# rc2014_6502.net
KiCad netlist of a schematic drawn in EAGLE
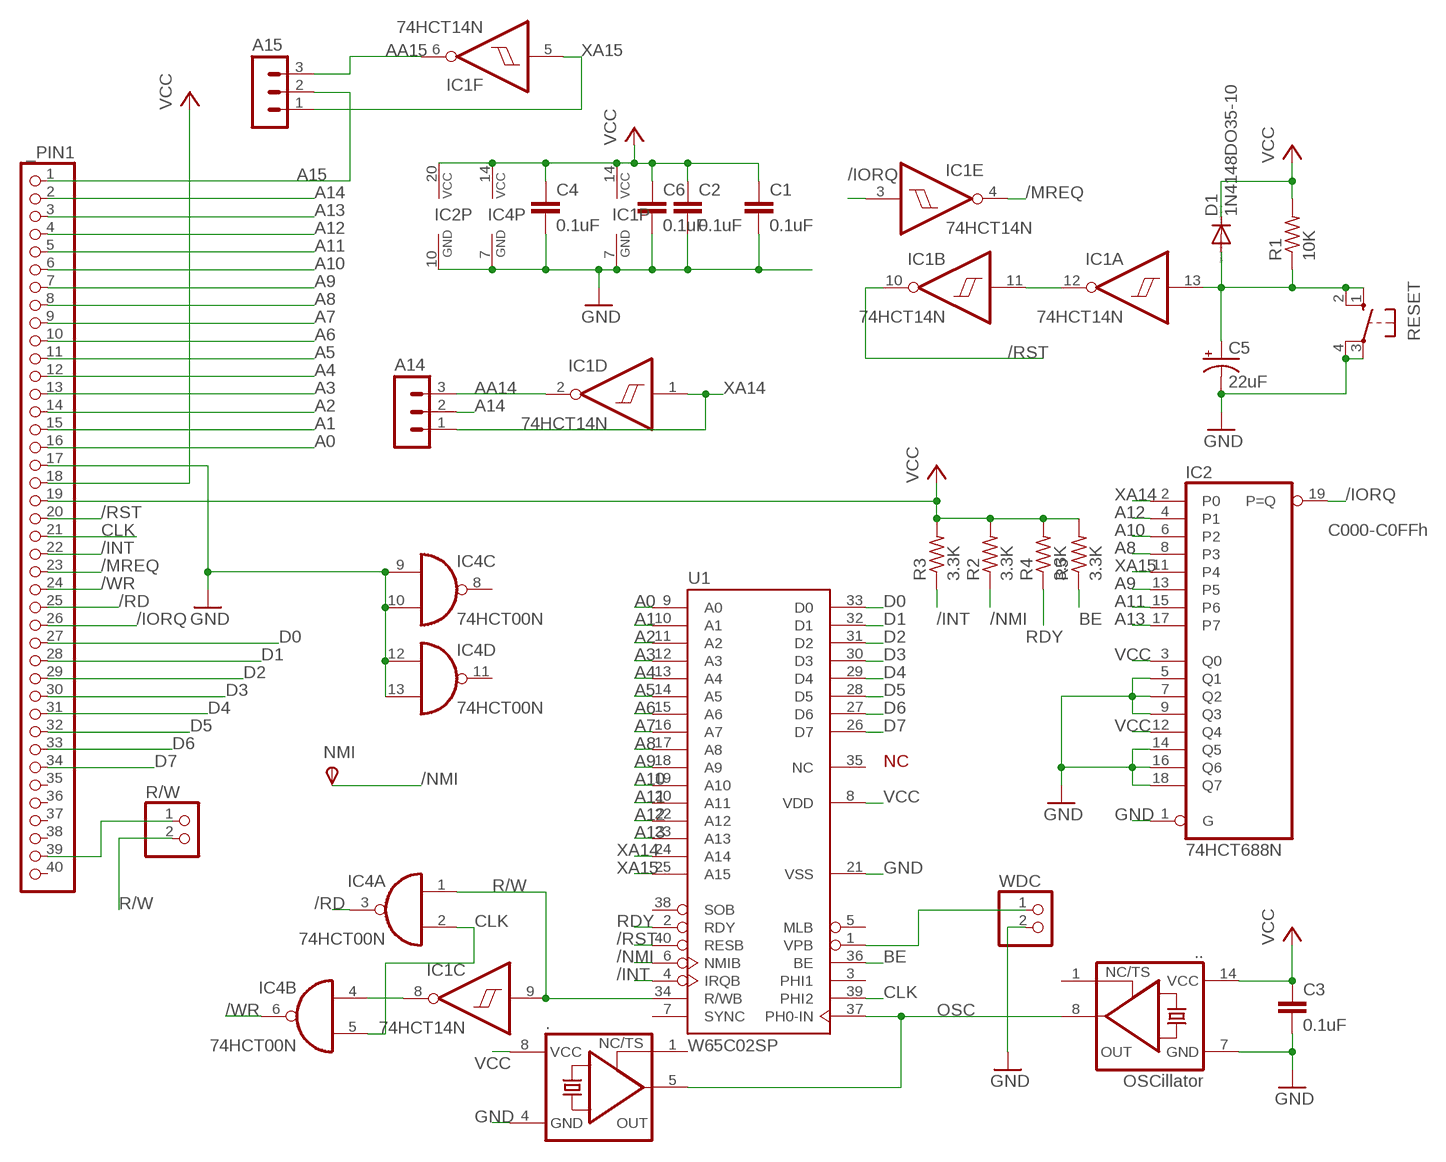
[diagram p0: schematic, sheet 1]

(export (version "E")
  (design (tool "Eeschema 10.0.6"))
  (components
    (comp (ref ".")
      (value "XO-8")
      (footprint "eagle-import:DIL08S")
      (libsource (lib "eagle-import") (part "XO-8"))
    )
    (comp (ref "..")
      (value "OSCillator")
      (footprint "eagle-import:DIL14S")
      (libsource (lib "eagle-import") (part "XO-14"))
    )
    (comp (ref "A14")
      (value "MA03-1")
      (footprint "eagle-import:MA03-1")
      (libsource (lib "eagle-import") (part "MA03-1"))
    )
    (comp (ref "A15")
      (value "MA03-1")
      (footprint "eagle-import:MA03-1")
      (libsource (lib "eagle-import") (part "MA03-1"))
    )
    (comp (ref "C1")
      (value "0.1uF")
      (footprint "eagle-import:C050-024X044")
      (libsource (lib "eagle-import") (part "C-EU050-024X044"))
    )
    (comp (ref "C2")
      (value "0.1uF")
      (footprint "eagle-import:C050-024X044")
      (libsource (lib "eagle-import") (part "C-EU050-024X044"))
    )
    (comp (ref "C3")
      (value "0.1uF")
      (footprint "eagle-import:C050-024X044")
      (libsource (lib "eagle-import") (part "C-EU050-024X044"))
    )
    (comp (ref "C4")
      (value "0.1uF")
      (footprint "eagle-import:C050-024X044")
      (libsource (lib "eagle-import") (part "C-EU050-024X044"))
    )
    (comp (ref "C5")
      (value "22uF")
      (footprint "eagle-import:TAP5-80")
      (libsource (lib "eagle-import") (part "CPOL-USTAP5-80"))
    )
    (comp (ref "C6")
      (value "0.1uF")
      (footprint "eagle-import:C050-024X044")
      (libsource (lib "eagle-import") (part "C-EU050-024X044"))
    )
    (comp (ref "D1")
      (value "1N4148DO35-10")
      (footprint "eagle-import:DO35-10")
      (libsource (lib "eagle-import") (part "1N4148DO35-10"))
    )
    (comp (ref "IC1")
      (value "74HCT14N")
      (footprint "eagle-import:DIL14")
      (libsource (lib "eagle-import") (part "7414NHCT"))
    )
    (comp (ref "IC2")
      (value "74HCT688N")
      (footprint "eagle-import:DIL20")
      (libsource (lib "eagle-import") (part "74688NHCT"))
    )
    (comp (ref "IC4")
      (value "74HCT00N")
      (footprint "eagle-import:DIL14")
      (libsource (lib "eagle-import") (part "7400NHCT"))
    )
    (comp (ref "NMI")
      (value "TPSPAD1-13")
      (footprint "eagle-import:P1-13")
      (libsource (lib "eagle-import") (part "TPSPAD1-13"))
    )
    (comp (ref "R/W")
      (value "PINHD-1X2")
      (footprint "eagle-import:1X02")
      (libsource (lib "eagle-import") (part "PINHD-1X2"))
    )
    (comp (ref "R1")
      (value "10K")
      (footprint "eagle-import:0207_10")
      (libsource (lib "eagle-import") (part "R-US_0207/10"))
    )
    (comp (ref "R2")
      (value "3.3K")
      (footprint "eagle-import:0207_10")
      (libsource (lib "eagle-import") (part "R-US_0207/10"))
    )
    (comp (ref "R3")
      (value "3.3K")
      (footprint "eagle-import:0207_10")
      (libsource (lib "eagle-import") (part "R-US_0207/10"))
    )
    (comp (ref "R4")
      (value "3.3K")
      (footprint "eagle-import:0207_10")
      (libsource (lib "eagle-import") (part "R-US_0207/10"))
    )
    (comp (ref "R5")
      (value "3.3K")
      (footprint "eagle-import:0207_10")
      (libsource (lib "eagle-import") (part "R-US_0207/10"))
    )
    (comp (ref "RESET")
      (value "10-XX")
      (footprint "eagle-import:B3F-10XX")
      (fields (field (name "MPN") "B3F-1000"))
      (libsource (lib "eagle-import") (part "10-XX"))
    )
    (comp (ref "U1")
      (value "W65C02SP")
      (footprint "eagle-import:DIP-40")
      (libsource (lib "eagle-import") (part "W65C02SP"))
    )
    (comp (ref "WDC")
      (value "PINHD-1X2")
      (footprint "eagle-import:1X02")
      (libsource (lib "eagle-import") (part "PINHD-1X2"))
    )
    (comp (ref "_PIN1")
      (value "PINHD-1X40")
      (footprint "eagle-import:1X40")
      (libsource (lib "eagle-import") (part "PINHD-1X40"))
    )
  )
  (nets
    (net (code "1") (name "/A0") (class "Default")
      (node (ref "U1") (pin "9") (pinfunction "A0_9") (pintype "bidirectional"))
      (node (ref "_PIN1") (pin "16") (pinfunction "16_16") (pintype "passive"))
    )
    (net (code "2") (name "/A1") (class "Default")
      (node (ref "U1") (pin "10") (pinfunction "A1_10") (pintype "bidirectional"))
      (node (ref "_PIN1") (pin "15") (pinfunction "15_15") (pintype "passive"))
    )
    (net (code "3") (name "/A2") (class "Default")
      (node (ref "U1") (pin "11") (pinfunction "A2_11") (pintype "bidirectional"))
      (node (ref "_PIN1") (pin "14") (pinfunction "14_14") (pintype "passive"))
    )
    (net (code "4") (name "/A3") (class "Default")
      (node (ref "U1") (pin "12") (pinfunction "A3_12") (pintype "bidirectional"))
      (node (ref "_PIN1") (pin "13") (pinfunction "13_13") (pintype "passive"))
    )
    (net (code "5") (name "/A4") (class "Default")
      (node (ref "U1") (pin "13") (pinfunction "A4_13") (pintype "bidirectional"))
      (node (ref "_PIN1") (pin "12") (pinfunction "12_12") (pintype "passive"))
    )
    (net (code "6") (name "/A5") (class "Default")
      (node (ref "U1") (pin "14") (pinfunction "A5_14") (pintype "bidirectional"))
      (node (ref "_PIN1") (pin "11") (pinfunction "11_11") (pintype "passive"))
    )
    (net (code "7") (name "/A6") (class "Default")
      (node (ref "U1") (pin "15") (pinfunction "A6_15") (pintype "bidirectional"))
      (node (ref "_PIN1") (pin "10") (pinfunction "10_10") (pintype "passive"))
    )
    (net (code "8") (name "/A7") (class "Default")
      (node (ref "U1") (pin "16") (pinfunction "A7_16") (pintype "bidirectional"))
      (node (ref "_PIN1") (pin "9") (pinfunction "9_9") (pintype "passive"))
    )
    (net (code "9") (name "/A8") (class "Default")
      (node (ref "IC2") (pin "8") (pinfunction "P3_8") (pintype "input"))
      (node (ref "U1") (pin "17") (pinfunction "A8_17") (pintype "bidirectional"))
      (node (ref "_PIN1") (pin "8") (pinfunction "8_8") (pintype "passive"))
    )
    (net (code "10") (name "/A9") (class "Default")
      (node (ref "IC2") (pin "13") (pinfunction "P5_13") (pintype "input"))
      (node (ref "U1") (pin "18") (pinfunction "A9_18") (pintype "bidirectional"))
      (node (ref "_PIN1") (pin "7") (pinfunction "7_7") (pintype "passive"))
    )
    (net (code "11") (name "/A10") (class "Default")
      (node (ref "IC2") (pin "6") (pinfunction "P2_6") (pintype "input"))
      (node (ref "U1") (pin "19") (pinfunction "A10_19") (pintype "bidirectional"))
      (node (ref "_PIN1") (pin "6") (pinfunction "6_6") (pintype "passive"))
    )
    (net (code "12") (name "/A11") (class "Default")
      (node (ref "IC2") (pin "15") (pinfunction "P6_15") (pintype "input"))
      (node (ref "U1") (pin "20") (pinfunction "A11_20") (pintype "bidirectional"))
      (node (ref "_PIN1") (pin "5") (pinfunction "5_5") (pintype "passive"))
    )
    (net (code "13") (name "/A12") (class "Default")
      (node (ref "IC2") (pin "4") (pinfunction "P1_4") (pintype "input"))
      (node (ref "U1") (pin "22") (pinfunction "A12_22") (pintype "bidirectional"))
      (node (ref "_PIN1") (pin "4") (pinfunction "4_4") (pintype "passive"))
    )
    (net (code "14") (name "/A13") (class "Default")
      (node (ref "IC2") (pin "17") (pinfunction "P7_17") (pintype "input"))
      (node (ref "U1") (pin "23") (pinfunction "A13_23") (pintype "bidirectional"))
      (node (ref "_PIN1") (pin "3") (pinfunction "3_3") (pintype "passive"))
    )
    (net (code "15") (name "/A14") (class "Default")
      (node (ref "A14") (pin "2") (pinfunction "2_2") (pintype "passive"))
      (node (ref "_PIN1") (pin "2") (pinfunction "2_2") (pintype "passive"))
    )
    (net (code "16") (name "/A15") (class "Default")
      (node (ref "A15") (pin "2") (pinfunction "2_2") (pintype "passive"))
      (node (ref "_PIN1") (pin "1") (pinfunction "1_1") (pintype "passive"))
    )
    (net (code "17") (name "/AA14") (class "Default")
      (node (ref "A14") (pin "3") (pinfunction "3_3") (pintype "passive"))
      (node (ref "IC1") (pin "2") (pinfunction "O_2") (pintype "output"))
    )
    (net (code "18") (name "/AA15") (class "Default")
      (node (ref "A15") (pin "3") (pinfunction "3_3") (pintype "passive"))
      (node (ref "IC1") (pin "6") (pinfunction "O_6") (pintype "output"))
    )
    (net (code "19") (name "/BE") (class "Default")
      (node (ref "R5") (pin "1") (pinfunction "1_1") (pintype "passive"))
      (node (ref "U1") (pin "36") (pinfunction "BE_36") (pintype "input"))
    )
    (net (code "20") (name "/CLK") (class "Default")
      (node (ref "IC4") (pin "2") (pinfunction "I1_2") (pintype "input"))
      (node (ref "IC4") (pin "5") (pinfunction "I1_5") (pintype "input"))
      (node (ref "U1") (pin "39") (pinfunction "PHI2_39") (pintype "output"))
      (node (ref "_PIN1") (pin "21") (pinfunction "21_21") (pintype "passive"))
    )
    (net (code "21") (name "/D0") (class "Default")
      (node (ref "U1") (pin "33") (pinfunction "D0_33") (pintype "bidirectional"))
      (node (ref "_PIN1") (pin "27") (pinfunction "27_27") (pintype "passive"))
    )
    (net (code "22") (name "/D1") (class "Default")
      (node (ref "U1") (pin "32") (pinfunction "D1_32") (pintype "bidirectional"))
      (node (ref "_PIN1") (pin "28") (pinfunction "28_28") (pintype "passive"))
    )
    (net (code "23") (name "/D2") (class "Default")
      (node (ref "U1") (pin "31") (pinfunction "D2_31") (pintype "bidirectional"))
      (node (ref "_PIN1") (pin "29") (pinfunction "29_29") (pintype "passive"))
    )
    (net (code "24") (name "/D3") (class "Default")
      (node (ref "U1") (pin "30") (pinfunction "D3_30") (pintype "bidirectional"))
      (node (ref "_PIN1") (pin "30") (pinfunction "30_30") (pintype "passive"))
    )
    (net (code "25") (name "/D4") (class "Default")
      (node (ref "U1") (pin "29") (pinfunction "D4_29") (pintype "bidirectional"))
      (node (ref "_PIN1") (pin "31") (pinfunction "31_31") (pintype "passive"))
    )
    (net (code "26") (name "/D5") (class "Default")
      (node (ref "U1") (pin "28") (pinfunction "D5_28") (pintype "bidirectional"))
      (node (ref "_PIN1") (pin "32") (pinfunction "32_32") (pintype "passive"))
    )
    (net (code "27") (name "/D6") (class "Default")
      (node (ref "U1") (pin "27") (pinfunction "D6_27") (pintype "bidirectional"))
      (node (ref "_PIN1") (pin "33") (pinfunction "33_33") (pintype "passive"))
    )
    (net (code "28") (name "/D7") (class "Default")
      (node (ref "U1") (pin "26") (pinfunction "D7_26") (pintype "bidirectional"))
      (node (ref "_PIN1") (pin "34") (pinfunction "34_34") (pintype "passive"))
    )
    (net (code "29") (name "/OSC") (class "Default")
      (node (ref ".") (pin "5") (pinfunction "OUT_5") (pintype "output"))
      (node (ref "..") (pin "8") (pinfunction "OUT_8") (pintype "output"))
      (node (ref "U1") (pin "37") (pinfunction "PH0-IN_37") (pintype "input"))
    )
    (net (code "30") (name "/RDY") (class "Default")
      (node (ref "R4") (pin "1") (pinfunction "1_1") (pintype "passive"))
      (node (ref "U1") (pin "2") (pinfunction "RDY_2") (pintype "bidirectional"))
    )
    (net (code "31") (name "/R{slash}W") (class "Default")
      (node (ref "IC1") (pin "9") (pinfunction "I_9") (pintype "input"))
      (node (ref "IC4") (pin "1") (pinfunction "I0_1") (pintype "input"))
      (node (ref "R/W") (pin "2") (pinfunction "2_2") (pintype "passive"))
      (node (ref "U1") (pin "34") (pinfunction "R/WB_34") (pintype "output"))
    )
    (net (code "32") (name "/XA14") (class "Default")
      (node (ref "A14") (pin "1") (pinfunction "1_1") (pintype "passive"))
      (node (ref "IC1") (pin "1") (pinfunction "I_1") (pintype "input"))
      (node (ref "IC2") (pin "2") (pinfunction "P0_2") (pintype "input"))
      (node (ref "U1") (pin "24") (pinfunction "A14_24") (pintype "bidirectional"))
    )
    (net (code "33") (name "/XA15") (class "Default")
      (node (ref "A15") (pin "1") (pinfunction "1_1") (pintype "passive"))
      (node (ref "IC1") (pin "5") (pinfunction "I_5") (pintype "input"))
      (node (ref "IC2") (pin "11") (pinfunction "P4_11") (pintype "input"))
      (node (ref "U1") (pin "25") (pinfunction "A15_25") (pintype "bidirectional"))
    )
    (net (code "34") (name "/{slash}INT") (class "Default")
      (node (ref "R3") (pin "1") (pinfunction "1_1") (pintype "passive"))
      (node (ref "U1") (pin "4") (pinfunction "IRQB_4") (pintype "input"))
      (node (ref "_PIN1") (pin "22") (pinfunction "22_22") (pintype "passive"))
    )
    (net (code "35") (name "/{slash}IORQ") (class "Default")
      (node (ref "IC1") (pin "3") (pinfunction "I_3") (pintype "input"))
      (node (ref "IC2") (pin "19") (pinfunction "P=Q_19") (pintype "output"))
      (node (ref "_PIN1") (pin "26") (pinfunction "26_26") (pintype "passive"))
    )
    (net (code "36") (name "/{slash}MREQ") (class "Default")
      (node (ref "IC1") (pin "4") (pinfunction "O_4") (pintype "output"))
      (node (ref "_PIN1") (pin "23") (pinfunction "23_23") (pintype "passive"))
    )
    (net (code "37") (name "/{slash}NMI") (class "Default")
      (node (ref "NMI") (pin "TP") (pinfunction "PP_TP") (pintype "input"))
      (node (ref "R2") (pin "1") (pinfunction "1_1") (pintype "passive"))
      (node (ref "U1") (pin "6") (pinfunction "NMIB_6") (pintype "input"))
    )
    (net (code "38") (name "/{slash}RD") (class "Default")
      (node (ref "IC4") (pin "3") (pinfunction "O_3") (pintype "output"))
      (node (ref "_PIN1") (pin "25") (pinfunction "25_25") (pintype "passive"))
    )
    (net (code "39") (name "/{slash}RST") (class "Default")
      (node (ref "IC1") (pin "10") (pinfunction "O_10") (pintype "output"))
      (node (ref "U1") (pin "40") (pinfunction "RESB_40") (pintype "input"))
      (node (ref "_PIN1") (pin "20") (pinfunction "20_20") (pintype "passive"))
    )
    (net (code "40") (name "/{slash}WR") (class "Default")
      (node (ref "IC4") (pin "6") (pinfunction "O_6") (pintype "output"))
      (node (ref "_PIN1") (pin "24") (pinfunction "24_24") (pintype "passive"))
    )
    (net (code "41") (name "GND") (class "Default")
      (node (ref ".") (pin "4") (pinfunction "GND_4") (pintype "power_in"))
      (node (ref "..") (pin "7") (pinfunction "GND_7") (pintype "power_in"))
      (node (ref "C1") (pin "2") (pinfunction "2_2") (pintype "passive"))
      (node (ref "C2") (pin "2") (pinfunction "2_2") (pintype "passive"))
      (node (ref "C3") (pin "2") (pinfunction "2_2") (pintype "passive"))
      (node (ref "C4") (pin "2") (pinfunction "2_2") (pintype "passive"))
      (node (ref "C5") (pin "-") (pinfunction "-_-") (pintype "passive"))
      (node (ref "C6") (pin "2") (pinfunction "2_2") (pintype "passive"))
      (node (ref "IC1") (pin "7") (pinfunction "GND_7") (pintype "power_in"))
      (node (ref "IC2") (pin "1") (pinfunction "G_1") (pintype "input"))
      (node (ref "IC2") (pin "10") (pinfunction "GND_10") (pintype "power_in"))
      (node (ref "IC2") (pin "14") (pinfunction "Q5_14") (pintype "input"))
      (node (ref "IC2") (pin "16") (pinfunction "Q6_16") (pintype "input"))
      (node (ref "IC2") (pin "18") (pinfunction "Q7_18") (pintype "input"))
      (node (ref "IC2") (pin "5") (pinfunction "Q1_5") (pintype "input"))
      (node (ref "IC2") (pin "7") (pinfunction "Q2_7") (pintype "input"))
      (node (ref "IC2") (pin "9") (pinfunction "Q3_9") (pintype "input"))
      (node (ref "IC4") (pin "10") (pinfunction "I1_10") (pintype "input"))
      (node (ref "IC4") (pin "12") (pinfunction "I0_12") (pintype "input"))
      (node (ref "IC4") (pin "13") (pinfunction "I1_13") (pintype "input"))
      (node (ref "IC4") (pin "7") (pinfunction "GND_7") (pintype "power_in"))
      (node (ref "IC4") (pin "9") (pinfunction "I0_9") (pintype "input"))
      (node (ref "RESET") (pin "3") (pinfunction "P_3") (pintype "passive"))
      (node (ref "RESET") (pin "4") (pinfunction "P1_4") (pintype "passive"))
      (node (ref "U1") (pin "21") (pinfunction "VSS_21") (pintype "power_in"))
      (node (ref "WDC") (pin "2") (pinfunction "2_2") (pintype "passive"))
      (node (ref "_PIN1") (pin "17") (pinfunction "17_17") (pintype "passive"))
    )
    (net (code "42") (name "Net-(IC1A-I)") (class "Default")
      (node (ref "C5") (pin "+") (pinfunction "+_+") (pintype "passive"))
      (node (ref "D1") (pin "A") (pinfunction "A_A") (pintype "passive"))
      (node (ref "IC1") (pin "13") (pinfunction "I_13") (pintype "input"))
      (node (ref "R1") (pin "1") (pinfunction "1_1") (pintype "passive"))
      (node (ref "RESET") (pin "1") (pinfunction "S_1") (pintype "passive"))
      (node (ref "RESET") (pin "2") (pinfunction "S1_2") (pintype "passive"))
    )
    (net (code "43") (name "Net-(IC1A-O)") (class "Default")
      (node (ref "IC1") (pin "11") (pinfunction "I_11") (pintype "input"))
      (node (ref "IC1") (pin "12") (pinfunction "O_12") (pintype "output"))
    )
    (net (code "44") (name "Net-(IC1C-O)") (class "Default")
      (node (ref "IC1") (pin "8") (pinfunction "O_8") (pintype "output"))
      (node (ref "IC4") (pin "4") (pinfunction "I0_4") (pintype "input"))
    )
    (net (code "45") (name "Net-(R/W-Pad1)") (class "Default")
      (node (ref "R/W") (pin "1") (pinfunction "1_1") (pintype "passive"))
      (node (ref "_PIN1") (pin "39") (pinfunction "39_39") (pintype "passive"))
    )
    (net (code "46") (name "Net-(U1-VPB)") (class "Default")
      (node (ref "U1") (pin "1") (pinfunction "VPB_1") (pintype "output"))
      (node (ref "WDC") (pin "1") (pinfunction "1_1") (pintype "passive"))
    )
    (net (code "47") (name "VCC") (class "Default")
      (node (ref ".") (pin "8") (pinfunction "VCC_8") (pintype "power_in"))
      (node (ref "..") (pin "14") (pinfunction "VCC_14") (pintype "power_in"))
      (node (ref "C1") (pin "1") (pinfunction "1_1") (pintype "passive"))
      (node (ref "C2") (pin "1") (pinfunction "1_1") (pintype "passive"))
      (node (ref "C3") (pin "1") (pinfunction "1_1") (pintype "passive"))
      (node (ref "C4") (pin "1") (pinfunction "1_1") (pintype "passive"))
      (node (ref "C6") (pin "1") (pinfunction "1_1") (pintype "passive"))
      (node (ref "D1") (pin "C") (pinfunction "C_C") (pintype "passive"))
      (node (ref "IC1") (pin "14") (pinfunction "VCC_14") (pintype "power_in"))
      (node (ref "IC2") (pin "12") (pinfunction "Q4_12") (pintype "input"))
      (node (ref "IC2") (pin "20") (pinfunction "VCC_20") (pintype "power_in"))
      (node (ref "IC2") (pin "3") (pinfunction "Q0_3") (pintype "input"))
      (node (ref "IC4") (pin "14") (pinfunction "VCC_14") (pintype "power_in"))
      (node (ref "R1") (pin "2") (pinfunction "2_2") (pintype "passive"))
      (node (ref "R2") (pin "2") (pinfunction "2_2") (pintype "passive"))
      (node (ref "R3") (pin "2") (pinfunction "2_2") (pintype "passive"))
      (node (ref "R4") (pin "2") (pinfunction "2_2") (pintype "passive"))
      (node (ref "R5") (pin "2") (pinfunction "2_2") (pintype "passive"))
      (node (ref "U1") (pin "8") (pinfunction "VDD_8") (pintype "power_in"))
      (node (ref "_PIN1") (pin "18") (pinfunction "18_18") (pintype "passive"))
      (node (ref "_PIN1") (pin "19") (pinfunction "19_19") (pintype "passive"))
    )
    (net (code "48") (name "unconnected-(.-TS-Pad1)") (class "Default")
      (node (ref ".") (pin "1") (pinfunction "TS_1") (pintype "passive"))
    )
    (net (code "49") (name "unconnected-(..-TS-Pad1)") (class "Default")
      (node (ref "..") (pin "1") (pinfunction "TS_1") (pintype "passive"))
    )
    (net (code "50") (name "unconnected-(IC4C-O-Pad8)") (class "Default")
      (node (ref "IC4") (pin "8") (pinfunction "O_8") (pintype "output"))
    )
    (net (code "51") (name "unconnected-(IC4D-O-Pad11)") (class "Default")
      (node (ref "IC4") (pin "11") (pinfunction "O_11") (pintype "output"))
    )
    (net (code "52") (name "unconnected-(U1-MLB-Pad5)") (class "Default")
      (node (ref "U1") (pin "5") (pinfunction "MLB_5") (pintype "output"))
    )
    (net (code "53") (name "unconnected-(U1-NC-Pad35)") (class "Default")
      (node (ref "U1") (pin "35") (pinfunction "NC_35") (pintype "no_connect"))
    )
    (net (code "54") (name "unconnected-(U1-PHI1-Pad3)") (class "Default")
      (node (ref "U1") (pin "3") (pinfunction "PHI1_3") (pintype "output"))
    )
    (net (code "55") (name "unconnected-(U1-SOB-Pad38)") (class "Default")
      (node (ref "U1") (pin "38") (pinfunction "SOB_38") (pintype "input"))
    )
    (net (code "56") (name "unconnected-(U1-SYNC-Pad7)") (class "Default")
      (node (ref "U1") (pin "7") (pinfunction "SYNC_7") (pintype "output"))
    )
    (net (code "57") (name "unconnected-(_PIN1-Pad35)") (class "Default")
      (node (ref "_PIN1") (pin "35") (pinfunction "35_35") (pintype "passive"))
    )
    (net (code "58") (name "unconnected-(_PIN1-Pad36)") (class "Default")
      (node (ref "_PIN1") (pin "36") (pinfunction "36_36") (pintype "passive"))
    )
    (net (code "59") (name "unconnected-(_PIN1-Pad37)") (class "Default")
      (node (ref "_PIN1") (pin "37") (pinfunction "37_37") (pintype "passive"))
    )
    (net (code "60") (name "unconnected-(_PIN1-Pad38)") (class "Default")
      (node (ref "_PIN1") (pin "38") (pinfunction "38_38") (pintype "passive"))
    )
    (net (code "61") (name "unconnected-(_PIN1-Pad40)") (class "Default")
      (node (ref "_PIN1") (pin "40") (pinfunction "40_40") (pintype "passive"))
    )
  )
)
